# eagle_whitestar-adapter-ta.net
KiCad netlist of a schematic drawn in EAGLE
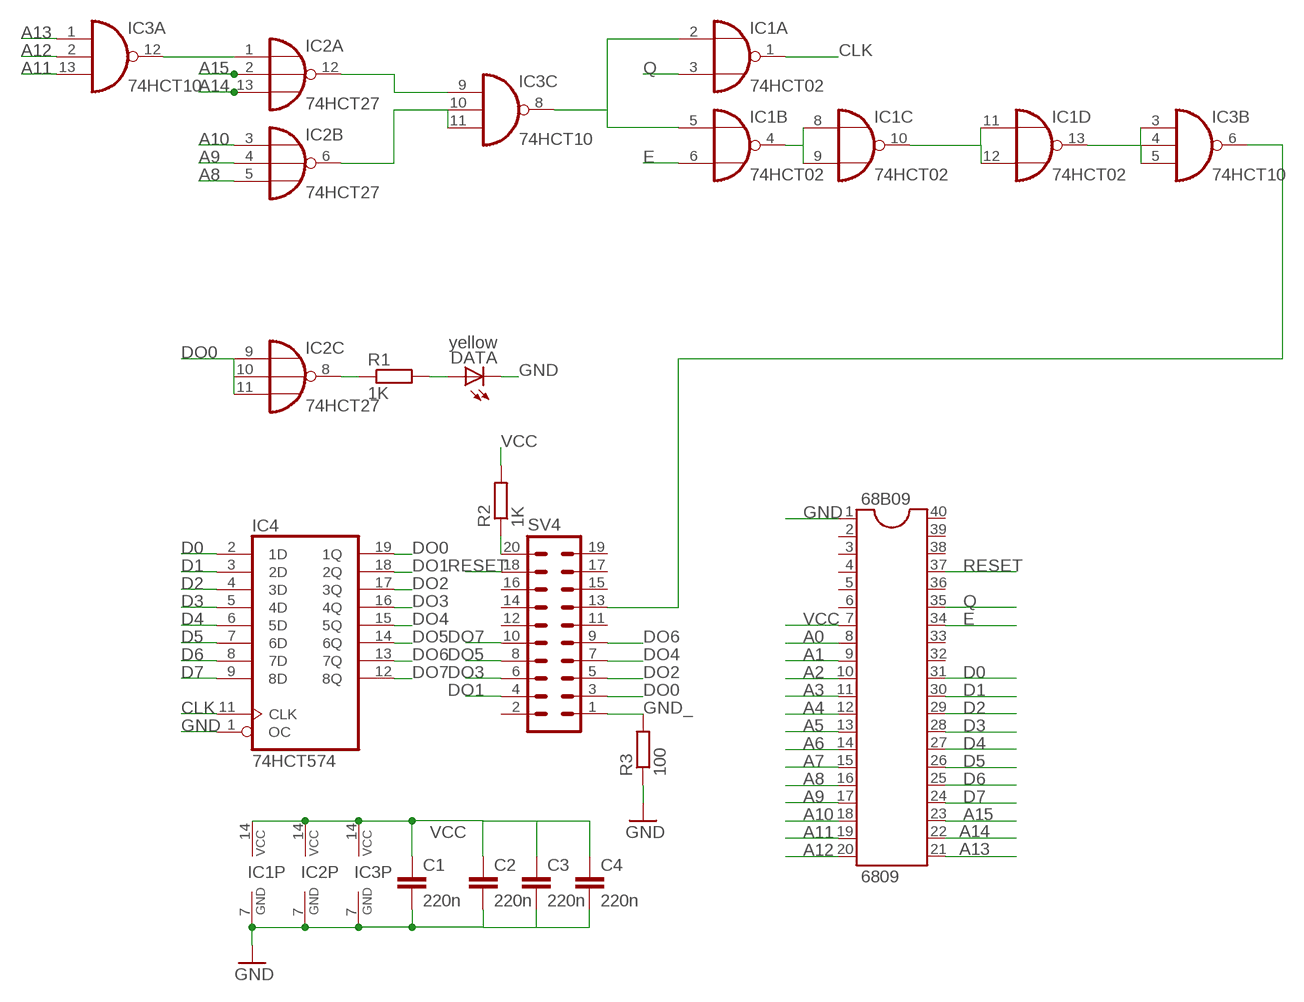
[diagram p0: schematic, sheet 1]

(export (version "E")
  (design (tool "Eeschema 10.0.6"))
  (components
    (comp (ref "68B09")
      (value "6809")
      (footprint "eagle-import:DIL40")
      (libsource (lib "eagle-import") (part "DIL40"))
    )
    (comp (ref "C1")
      (value "220n")
      (footprint "eagle-import:C0603K")
      (libsource (lib "eagle-import") (part "C-EUC0603K"))
    )
    (comp (ref "C2")
      (value "220n")
      (footprint "eagle-import:C0603K")
      (libsource (lib "eagle-import") (part "C-EUC0603K"))
    )
    (comp (ref "C3")
      (value "220n")
      (footprint "eagle-import:C0603K")
      (libsource (lib "eagle-import") (part "C-EUC0603K"))
    )
    (comp (ref "C4")
      (value "220n")
      (footprint "eagle-import:C0603K")
      (libsource (lib "eagle-import") (part "C-EUC0603K"))
    )
    (comp (ref "DATA")
      (value "yellow")
      (footprint "eagle-import:SML0603")
      (libsource (lib "eagle-import") (part "LEDSML0603"))
    )
    (comp (ref "IC1")
      (value "74HCT02")
      (footprint "eagle-import:SO14")
      (libsource (lib "eagle-import") (part "7402DHCT"))
    )
    (comp (ref "IC2")
      (value "74HCT27")
      (footprint "eagle-import:SO14")
      (libsource (lib "eagle-import") (part "7427DHCT"))
    )
    (comp (ref "IC3")
      (value "74HCT10")
      (footprint "eagle-import:SO14")
      (libsource (lib "eagle-import") (part "7410DAC"))
    )
    (comp (ref "IC4")
      (value "74HCT574")
      (footprint "eagle-import:SO20W")
      (libsource (lib "eagle-import") (part "74574DHCT"))
    )
    (comp (ref "R1")
      (value "1K")
      (footprint "eagle-import:R0603")
      (libsource (lib "eagle-import") (part "R-EU_R0603"))
    )
    (comp (ref "R2")
      (value "1K")
      (footprint "eagle-import:R0603")
      (libsource (lib "eagle-import") (part "R-EU_R0603"))
    )
    (comp (ref "R3")
      (value "100")
      (footprint "eagle-import:R0603")
      (libsource (lib "eagle-import") (part "R-EU_R0603"))
    )
    (comp (ref "SV4")
      (value "MA10-2")
      (footprint "eagle-import:MA10-2")
      (libsource (lib "eagle-import") (part "MA10-2"))
    )
  )
  (nets
    (net (code "1") (name "/A0") (class "Default")
      (node (ref "68B09") (pin "8") (pinfunction "8_8") (pintype "passive"))
    )
    (net (code "2") (name "/A1") (class "Default")
      (node (ref "68B09") (pin "9") (pinfunction "9_9") (pintype "passive"))
    )
    (net (code "3") (name "/A2") (class "Default")
      (node (ref "68B09") (pin "10") (pinfunction "10_10") (pintype "passive"))
    )
    (net (code "4") (name "/A3") (class "Default")
      (node (ref "68B09") (pin "11") (pinfunction "11_11") (pintype "passive"))
    )
    (net (code "5") (name "/A4") (class "Default")
      (node (ref "68B09") (pin "12") (pinfunction "12_12") (pintype "passive"))
    )
    (net (code "6") (name "/A5") (class "Default")
      (node (ref "68B09") (pin "13") (pinfunction "13_13") (pintype "passive"))
    )
    (net (code "7") (name "/A6") (class "Default")
      (node (ref "68B09") (pin "14") (pinfunction "14_14") (pintype "passive"))
    )
    (net (code "8") (name "/A7") (class "Default")
      (node (ref "68B09") (pin "15") (pinfunction "15_15") (pintype "passive"))
    )
    (net (code "9") (name "/A8") (class "Default")
      (node (ref "68B09") (pin "16") (pinfunction "16_16") (pintype "passive"))
      (node (ref "IC2") (pin "5") (pinfunction "I2_5") (pintype "input"))
    )
    (net (code "10") (name "/A9") (class "Default")
      (node (ref "68B09") (pin "17") (pinfunction "17_17") (pintype "passive"))
      (node (ref "IC2") (pin "4") (pinfunction "I1_4") (pintype "input"))
    )
    (net (code "11") (name "/A10") (class "Default")
      (node (ref "68B09") (pin "18") (pinfunction "18_18") (pintype "passive"))
      (node (ref "IC2") (pin "3") (pinfunction "I0_3") (pintype "input"))
    )
    (net (code "12") (name "/A11") (class "Default")
      (node (ref "68B09") (pin "19") (pinfunction "19_19") (pintype "passive"))
      (node (ref "IC3") (pin "13") (pinfunction "I2_13") (pintype "input"))
    )
    (net (code "13") (name "/A12") (class "Default")
      (node (ref "68B09") (pin "20") (pinfunction "20_20") (pintype "passive"))
      (node (ref "IC3") (pin "2") (pinfunction "I1_2") (pintype "input"))
    )
    (net (code "14") (name "/A13") (class "Default")
      (node (ref "68B09") (pin "21") (pinfunction "21_21") (pintype "passive"))
      (node (ref "IC3") (pin "1") (pinfunction "I0_1") (pintype "input"))
    )
    (net (code "15") (name "/A14") (class "Default")
      (node (ref "68B09") (pin "22") (pinfunction "22_22") (pintype "passive"))
      (node (ref "IC2") (pin "13") (pinfunction "I2_13") (pintype "input"))
    )
    (net (code "16") (name "/A15") (class "Default")
      (node (ref "68B09") (pin "23") (pinfunction "23_23") (pintype "passive"))
      (node (ref "IC2") (pin "2") (pinfunction "I1_2") (pintype "input"))
    )
    (net (code "17") (name "/CLK") (class "Default")
      (node (ref "IC1") (pin "1") (pinfunction "O_1") (pintype "output"))
      (node (ref "IC4") (pin "11") (pinfunction "CLK_11") (pintype "input"))
    )
    (net (code "18") (name "/D0") (class "Default")
      (node (ref "68B09") (pin "31") (pinfunction "31_31") (pintype "passive"))
      (node (ref "IC4") (pin "2") (pinfunction "1D_2") (pintype "input"))
    )
    (net (code "19") (name "/D1") (class "Default")
      (node (ref "68B09") (pin "30") (pinfunction "30_30") (pintype "passive"))
      (node (ref "IC4") (pin "3") (pinfunction "2D_3") (pintype "input"))
    )
    (net (code "20") (name "/D2") (class "Default")
      (node (ref "68B09") (pin "29") (pinfunction "29_29") (pintype "passive"))
      (node (ref "IC4") (pin "4") (pinfunction "3D_4") (pintype "input"))
    )
    (net (code "21") (name "/D3") (class "Default")
      (node (ref "68B09") (pin "28") (pinfunction "28_28") (pintype "passive"))
      (node (ref "IC4") (pin "5") (pinfunction "4D_5") (pintype "input"))
    )
    (net (code "22") (name "/D4") (class "Default")
      (node (ref "68B09") (pin "27") (pinfunction "27_27") (pintype "passive"))
      (node (ref "IC4") (pin "6") (pinfunction "5D_6") (pintype "input"))
    )
    (net (code "23") (name "/D5") (class "Default")
      (node (ref "68B09") (pin "26") (pinfunction "26_26") (pintype "passive"))
      (node (ref "IC4") (pin "7") (pinfunction "6D_7") (pintype "input"))
    )
    (net (code "24") (name "/D6") (class "Default")
      (node (ref "68B09") (pin "25") (pinfunction "25_25") (pintype "passive"))
      (node (ref "IC4") (pin "8") (pinfunction "7D_8") (pintype "input"))
    )
    (net (code "25") (name "/D7") (class "Default")
      (node (ref "68B09") (pin "24") (pinfunction "24_24") (pintype "passive"))
      (node (ref "IC4") (pin "9") (pinfunction "8D_9") (pintype "input"))
    )
    (net (code "26") (name "/DO0") (class "Default")
      (node (ref "IC2") (pin "10") (pinfunction "I1_10") (pintype "input"))
      (node (ref "IC2") (pin "11") (pinfunction "I2_11") (pintype "input"))
      (node (ref "IC2") (pin "9") (pinfunction "I0_9") (pintype "input"))
      (node (ref "IC4") (pin "19") (pinfunction "1Q_19") (pintype "tri_state"))
      (node (ref "SV4") (pin "3") (pinfunction "3_3") (pintype "passive"))
    )
    (net (code "27") (name "/DO1") (class "Default")
      (node (ref "IC4") (pin "18") (pinfunction "2Q_18") (pintype "tri_state"))
      (node (ref "SV4") (pin "4") (pinfunction "4_4") (pintype "passive"))
    )
    (net (code "28") (name "/DO2") (class "Default")
      (node (ref "IC4") (pin "17") (pinfunction "3Q_17") (pintype "tri_state"))
      (node (ref "SV4") (pin "5") (pinfunction "5_5") (pintype "passive"))
    )
    (net (code "29") (name "/DO3") (class "Default")
      (node (ref "IC4") (pin "16") (pinfunction "4Q_16") (pintype "tri_state"))
      (node (ref "SV4") (pin "6") (pinfunction "6_6") (pintype "passive"))
    )
    (net (code "30") (name "/DO4") (class "Default")
      (node (ref "IC4") (pin "15") (pinfunction "5Q_15") (pintype "tri_state"))
      (node (ref "SV4") (pin "7") (pinfunction "7_7") (pintype "passive"))
    )
    (net (code "31") (name "/DO5") (class "Default")
      (node (ref "IC4") (pin "14") (pinfunction "6Q_14") (pintype "tri_state"))
      (node (ref "SV4") (pin "8") (pinfunction "8_8") (pintype "passive"))
    )
    (net (code "32") (name "/DO6") (class "Default")
      (node (ref "IC4") (pin "13") (pinfunction "7Q_13") (pintype "tri_state"))
      (node (ref "SV4") (pin "9") (pinfunction "9_9") (pintype "passive"))
    )
    (net (code "33") (name "/DO7") (class "Default")
      (node (ref "IC4") (pin "12") (pinfunction "8Q_12") (pintype "tri_state"))
      (node (ref "SV4") (pin "10") (pinfunction "10_10") (pintype "passive"))
    )
    (net (code "34") (name "/E") (class "Default")
      (node (ref "68B09") (pin "34") (pinfunction "34_34") (pintype "passive"))
      (node (ref "IC1") (pin "6") (pinfunction "I1_6") (pintype "input"))
    )
    (net (code "35") (name "/GND_") (class "Default")
      (node (ref "R3") (pin "2") (pinfunction "2_2") (pintype "passive"))
      (node (ref "SV4") (pin "1") (pinfunction "1_1") (pintype "passive"))
    )
    (net (code "36") (name "/Q") (class "Default")
      (node (ref "68B09") (pin "35") (pinfunction "35_35") (pintype "passive"))
      (node (ref "IC1") (pin "3") (pinfunction "I1_3") (pintype "input"))
    )
    (net (code "37") (name "/RESET") (class "Default")
      (node (ref "68B09") (pin "37") (pinfunction "37_37") (pintype "passive"))
      (node (ref "SV4") (pin "18") (pinfunction "18_18") (pintype "passive"))
    )
    (net (code "38") (name "/VCC") (class "Default")
      (node (ref "68B09") (pin "7") (pinfunction "7_7") (pintype "passive"))
      (node (ref "C1") (pin "1") (pinfunction "1_1") (pintype "passive"))
      (node (ref "C2") (pin "1") (pinfunction "1_1") (pintype "passive"))
      (node (ref "C3") (pin "1") (pinfunction "1_1") (pintype "passive"))
      (node (ref "C4") (pin "1") (pinfunction "1_1") (pintype "passive"))
      (node (ref "IC1") (pin "14") (pinfunction "VCC_14") (pintype "power_in"))
      (node (ref "IC2") (pin "14") (pinfunction "VCC_14") (pintype "power_in"))
      (node (ref "IC3") (pin "14") (pinfunction "VCC_14") (pintype "power_in"))
      (node (ref "R2") (pin "2") (pinfunction "2_2") (pintype "passive"))
    )
    (net (code "39") (name "GND") (class "Default")
      (node (ref "68B09") (pin "1") (pinfunction "1_1") (pintype "passive"))
      (node (ref "C1") (pin "2") (pinfunction "2_2") (pintype "passive"))
      (node (ref "C2") (pin "2") (pinfunction "2_2") (pintype "passive"))
      (node (ref "C3") (pin "2") (pinfunction "2_2") (pintype "passive"))
      (node (ref "C4") (pin "2") (pinfunction "2_2") (pintype "passive"))
      (node (ref "DATA") (pin "C") (pinfunction "C_C") (pintype "passive"))
      (node (ref "IC1") (pin "7") (pinfunction "GND_7") (pintype "power_in"))
      (node (ref "IC2") (pin "7") (pinfunction "GND_7") (pintype "power_in"))
      (node (ref "IC3") (pin "7") (pinfunction "GND_7") (pintype "power_in"))
      (node (ref "IC4") (pin "1") (pinfunction "OC_1") (pintype "input"))
      (node (ref "R3") (pin "1") (pinfunction "1_1") (pintype "passive"))
    )
    (net (code "40") (name "Net-(DATA-PadA)") (class "Default")
      (node (ref "DATA") (pin "A") (pinfunction "A_A") (pintype "passive"))
      (node (ref "R1") (pin "2") (pinfunction "2_2") (pintype "passive"))
    )
    (net (code "41") (name "Net-(IC1A-I0)") (class "Default")
      (node (ref "IC1") (pin "2") (pinfunction "I0_2") (pintype "input"))
      (node (ref "IC1") (pin "5") (pinfunction "I0_5") (pintype "input"))
      (node (ref "IC3") (pin "8") (pinfunction "O_8") (pintype "output"))
    )
    (net (code "42") (name "Net-(IC1B-O)") (class "Default")
      (node (ref "IC1") (pin "4") (pinfunction "O_4") (pintype "output"))
      (node (ref "IC1") (pin "8") (pinfunction "I0_8") (pintype "input"))
      (node (ref "IC1") (pin "9") (pinfunction "I1_9") (pintype "input"))
    )
    (net (code "43") (name "Net-(IC1C-O)") (class "Default")
      (node (ref "IC1") (pin "10") (pinfunction "O_10") (pintype "output"))
      (node (ref "IC1") (pin "11") (pinfunction "I0_11") (pintype "input"))
      (node (ref "IC1") (pin "12") (pinfunction "I1_12") (pintype "input"))
    )
    (net (code "44") (name "Net-(IC1D-O)") (class "Default")
      (node (ref "IC1") (pin "13") (pinfunction "O_13") (pintype "output"))
      (node (ref "IC3") (pin "3") (pinfunction "I0_3") (pintype "input"))
      (node (ref "IC3") (pin "4") (pinfunction "I1_4") (pintype "input"))
      (node (ref "IC3") (pin "5") (pinfunction "I2_5") (pintype "input"))
    )
    (net (code "45") (name "Net-(IC2A-I0)") (class "Default")
      (node (ref "IC2") (pin "1") (pinfunction "I0_1") (pintype "input"))
      (node (ref "IC3") (pin "12") (pinfunction "O_12") (pintype "output"))
    )
    (net (code "46") (name "Net-(IC2A-O)") (class "Default")
      (node (ref "IC2") (pin "12") (pinfunction "O_12") (pintype "output"))
      (node (ref "IC3") (pin "9") (pinfunction "I0_9") (pintype "input"))
    )
    (net (code "47") (name "Net-(IC2B-O)") (class "Default")
      (node (ref "IC2") (pin "6") (pinfunction "O_6") (pintype "output"))
      (node (ref "IC3") (pin "10") (pinfunction "I1_10") (pintype "input"))
      (node (ref "IC3") (pin "11") (pinfunction "I2_11") (pintype "input"))
    )
    (net (code "48") (name "Net-(IC2C-O)") (class "Default")
      (node (ref "IC2") (pin "8") (pinfunction "O_8") (pintype "output"))
      (node (ref "R1") (pin "1") (pinfunction "1_1") (pintype "passive"))
    )
    (net (code "49") (name "Net-(IC3B-O)") (class "Default")
      (node (ref "IC3") (pin "6") (pinfunction "O_6") (pintype "output"))
      (node (ref "SV4") (pin "13") (pinfunction "13_13") (pintype "passive"))
    )
    (net (code "50") (name "Net-(R2-Pad1)") (class "Default")
      (node (ref "R2") (pin "1") (pinfunction "1_1") (pintype "passive"))
      (node (ref "SV4") (pin "20") (pinfunction "20_20") (pintype "passive"))
    )
    (net (code "51") (name "unconnected-(68B09-Pad2)") (class "Default")
      (node (ref "68B09") (pin "2") (pinfunction "2_2") (pintype "passive"))
    )
    (net (code "52") (name "unconnected-(68B09-Pad3)") (class "Default")
      (node (ref "68B09") (pin "3") (pinfunction "3_3") (pintype "passive"))
    )
    (net (code "53") (name "unconnected-(68B09-Pad4)") (class "Default")
      (node (ref "68B09") (pin "4") (pinfunction "4_4") (pintype "passive"))
    )
    (net (code "54") (name "unconnected-(68B09-Pad5)") (class "Default")
      (node (ref "68B09") (pin "5") (pinfunction "5_5") (pintype "passive"))
    )
    (net (code "55") (name "unconnected-(68B09-Pad6)") (class "Default")
      (node (ref "68B09") (pin "6") (pinfunction "6_6") (pintype "passive"))
    )
    (net (code "56") (name "unconnected-(68B09-Pad32)") (class "Default")
      (node (ref "68B09") (pin "32") (pinfunction "32_32") (pintype "passive"))
    )
    (net (code "57") (name "unconnected-(68B09-Pad33)") (class "Default")
      (node (ref "68B09") (pin "33") (pinfunction "33_33") (pintype "passive"))
    )
    (net (code "58") (name "unconnected-(68B09-Pad36)") (class "Default")
      (node (ref "68B09") (pin "36") (pinfunction "36_36") (pintype "passive"))
    )
    (net (code "59") (name "unconnected-(68B09-Pad38)") (class "Default")
      (node (ref "68B09") (pin "38") (pinfunction "38_38") (pintype "passive"))
    )
    (net (code "60") (name "unconnected-(68B09-Pad39)") (class "Default")
      (node (ref "68B09") (pin "39") (pinfunction "39_39") (pintype "passive"))
    )
    (net (code "61") (name "unconnected-(68B09-Pad40)") (class "Default")
      (node (ref "68B09") (pin "40") (pinfunction "40_40") (pintype "passive"))
    )
    (net (code "62") (name "unconnected-(SV4-Pad2)") (class "Default")
      (node (ref "SV4") (pin "2") (pinfunction "2_2") (pintype "passive"))
    )
    (net (code "63") (name "unconnected-(SV4-Pad11)") (class "Default")
      (node (ref "SV4") (pin "11") (pinfunction "11_11") (pintype "passive"))
    )
    (net (code "64") (name "unconnected-(SV4-Pad12)") (class "Default")
      (node (ref "SV4") (pin "12") (pinfunction "12_12") (pintype "passive"))
    )
    (net (code "65") (name "unconnected-(SV4-Pad14)") (class "Default")
      (node (ref "SV4") (pin "14") (pinfunction "14_14") (pintype "passive"))
    )
    (net (code "66") (name "unconnected-(SV4-Pad15)") (class "Default")
      (node (ref "SV4") (pin "15") (pinfunction "15_15") (pintype "passive"))
    )
    (net (code "67") (name "unconnected-(SV4-Pad16)") (class "Default")
      (node (ref "SV4") (pin "16") (pinfunction "16_16") (pintype "passive"))
    )
    (net (code "68") (name "unconnected-(SV4-Pad17)") (class "Default")
      (node (ref "SV4") (pin "17") (pinfunction "17_17") (pintype "passive"))
    )
    (net (code "69") (name "unconnected-(SV4-Pad19)") (class "Default")
      (node (ref "SV4") (pin "19") (pinfunction "19_19") (pintype "passive"))
    )
  )
)
